# Sheet1.net
KiCad netlist of a schematic drawn in Altium Designer
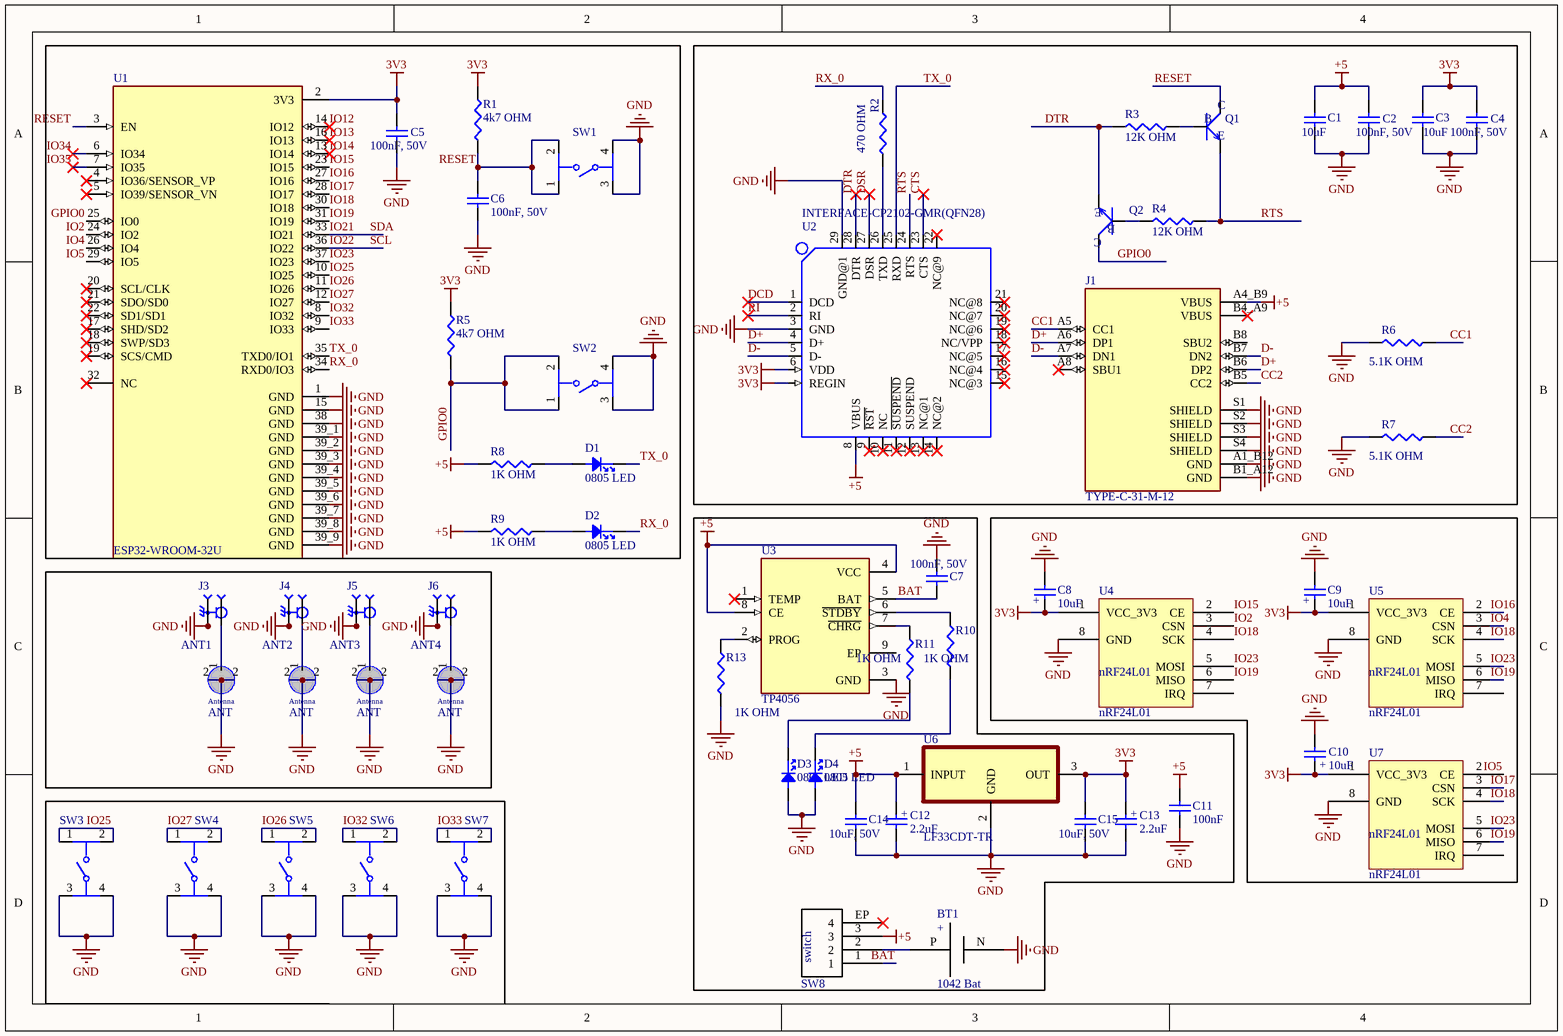
[diagram p0: Sheet1.SchDoc]

(export (version "E")
  (design (tool "Eeschema 10.0.6"))
  (components
    (comp (ref "ANT1")
      (value "ANT")
      (footprint "U.FL SMD")
      (description "U.FL Antenna")
      (libsource (lib "Schlib1") (part "ANT"))
    )
    (comp (ref "ANT2")
      (value "ANT")
      (footprint "U.FL SMD")
      (description "U.FL Antenna")
      (libsource (lib "Schlib1") (part "ANT"))
    )
    (comp (ref "ANT3")
      (value "ANT")
      (footprint "U.FL SMD")
      (description "U.FL Antenna")
      (libsource (lib "Schlib1") (part "ANT"))
    )
    (comp (ref "ANT4")
      (value "ANT")
      (footprint "U.FL SMD")
      (description "U.FL Antenna")
      (libsource (lib "Schlib1") (part "ANT"))
    )
    (comp (ref "BT1") (value "1042 Bat") (footprint "BAT_1042") (libsource (lib "Schlib1") (part "1042")))
    (comp (ref "C1")
      (value "10uF")
      (footprint "CAP0805")
      (description "CAP CER 10UF 0805")
      (fields
        (field (name "MANUFACTURER") "Samsung Electro-Mechanics")
        (field (name "MANUFACTURER PART NUMBER") "CL05B104KB5NNNC")
      )
      (libsource (lib "Schlib1") (part "C0805_10UF"))
    )
    (comp (ref "C2")
      (value "100nF, 50V")
      (footprint "CAP0805")
      (description "CAP CER 0.1UF 0805")
      (fields
        (field (name "MANUFACTURER") "Samsung Electro-Mechanics")
        (field (name "MANUFACTURER PART NUMBER") "CL05B104KB5NNNC")
      )
      (libsource (lib "Schlib1") (part "C0805 100nF"))
    )
    (comp (ref "C3")
      (value "10uF")
      (footprint "CAP0805")
      (description "CAP CER 10UF 0805")
      (fields
        (field (name "MANUFACTURER") "Samsung Electro-Mechanics")
        (field (name "MANUFACTURER PART NUMBER") "CL05B104KB5NNNC")
      )
      (libsource (lib "Schlib1") (part "C0805_10UF"))
    )
    (comp (ref "C4")
      (value "100nF, 50V")
      (footprint "CAP0805")
      (description "CAP CER 0.1UF 0805")
      (fields
        (field (name "MANUFACTURER") "Samsung Electro-Mechanics")
        (field (name "MANUFACTURER PART NUMBER") "CL05B104KB5NNNC")
      )
      (libsource (lib "Schlib1") (part "C0805 100nF"))
    )
    (comp (ref "C5")
      (value "100nF, 50V")
      (footprint "CAP0805")
      (description "CAP CER 0.1UF 0805")
      (fields
        (field (name "MANUFACTURER") "Samsung Electro-Mechanics")
        (field (name "MANUFACTURER PART NUMBER") "CL05B104KB5NNNC")
      )
      (libsource (lib "Schlib1") (part "C0805"))
    )
    (comp (ref "C6")
      (value "100nF, 50V")
      (footprint "CAP0805")
      (description "CAP CER 0.1UF 0805")
      (fields
        (field (name "MANUFACTURER") "Samsung Electro-Mechanics")
        (field (name "MANUFACTURER PART NUMBER") "CL05B104KB5NNNC")
      )
      (libsource (lib "Schlib1") (part "C0805"))
    )
    (comp (ref "C7")
      (value "100nF, 50V")
      (footprint "CAP0805")
      (description "CAP CER 0.1UF 0805")
      (fields
        (field (name "MANUFACTURER") "Samsung Electro-Mechanics")
        (field (name "MANUFACTURER PART NUMBER") "CL05B104KB5NNNC")
      )
      (libsource (lib "Schlib1") (part "C0805 100nF"))
    )
    (comp (ref "C8")
      (value "10uF")
      (footprint "Tan 1206 (3216X18L) Size A")
      (description "Capacitor Tantalum SMD")
      (libsource (lib "Schlib1") (part "10uF Capacitor Tantalum SMD"))
    )
    (comp (ref "C9")
      (value "10uF")
      (footprint "Tan 1206 (3216X18L) Size A")
      (description "Capacitor Tantalum SMD")
      (libsource (lib "Schlib1") (part "10uF Capacitor Tantalum SMD"))
    )
    (comp (ref "C10")
      (value "10uF")
      (footprint "Tan 1206 (3216X18L) Size A")
      (description "Capacitor Tantalum SMD")
      (libsource (lib "Schlib1") (part "Capacitor Tantalum SMD"))
    )
    (comp (ref "C11")
      (value "100nF")
      (footprint "CAP0805")
      (description "CAP CER 100nF 0805")
      (fields
        (field (name "MANUFACTURER") "Samsung Electro-Mechanics")
        (field (name "MANUFACTURER PART NUMBER") "CL05B104KB5NNNC")
      )
      (libsource (lib "Schlib1") (part "C0805_100nF"))
    )
    (comp (ref "C12")
      (value "2.2uF")
      (footprint "Tan 1206 (3216X18L) Size A")
      (description "Capacitor Tantalum SMD")
      (libsource (lib "Schlib1") (part "2.2uF Capacitor Tantalum SMD"))
    )
    (comp (ref "C13")
      (value "2.2uF")
      (footprint "Tan 1206 (3216X18L) Size A")
      (description "Capacitor Tantalum SMD")
      (libsource (lib "Schlib1") (part "2.2uF Capacitor Tantalum SMD"))
    )
    (comp (ref "C14")
      (value "10uF, 50V")
      (footprint "CAP 1206 (3216X15L)")
      (description "CAP CER 10uF 0805, 'CAP 1206 (3216X15L)")
      (fields
        (field (name "MANUFACTURER") "Samsung Electro-Mechanics")
        (field (name "MANUFACTURER PART NUMBER") "CL05B104KB5NNNC")
      )
      (libsource (lib "Schlib1") (part "CAP 10uF (3216X15L)"))
    )
    (comp (ref "C15")
      (value "10uF, 50V")
      (footprint "CAP 1206 (3216X15L)")
      (description "CAP CER 10uF 0805, 'CAP 1206 (3216X15L)")
      (fields
        (field (name "MANUFACTURER") "Samsung Electro-Mechanics")
        (field (name "MANUFACTURER PART NUMBER") "CL05B104KB5NNNC")
      )
      (libsource (lib "Schlib1") (part "CAP 10uF (3216X15L)"))
    )
    (comp (ref "D1")
      (value "0805 LED")
      (footprint "L0805")
      (description "LED RED 0805 SMD")
      (fields
        (field (name "MANUFACTURER") "Vishay")
        (field (name "MANUFACTURER PART NUMBER") "VLMS1500-GS08")
      )
      (libsource (lib "Schlib1") (part "LED 0805"))
    )
    (comp (ref "D2")
      (value "0805 LED")
      (footprint "L0805")
      (description "LED RED 0805 SMD")
      (fields
        (field (name "MANUFACTURER") "Vishay")
        (field (name "MANUFACTURER PART NUMBER") "VLMS1500-GS08")
      )
      (libsource (lib "Schlib1") (part "LED 0805"))
    )
    (comp (ref "D3")
      (value "0805 LED")
      (footprint "L0805")
      (description "LED RED 0805 SMD")
      (fields
        (field (name "MANUFACTURER") "Vishay")
        (field (name "MANUFACTURER PART NUMBER") "VLMS1500-GS08")
      )
      (libsource (lib "Schlib1") (part "LED 0805"))
    )
    (comp (ref "D4")
      (value "0805 LED")
      (footprint "L0805")
      (description "LED RED 0805 SMD")
      (fields
        (field (name "MANUFACTURER") "Vishay")
        (field (name "MANUFACTURER PART NUMBER") "VLMS1500-GS08")
      )
      (libsource (lib "Schlib1") (part "LED 0805"))
    )
    (comp (ref "J1")
      (value "TYPE-C-31-M-12")
      (footprint "HRO_TYPE-C-31-M-12")
      (description "USB Connectors 24 Receptacle 1 8.94*7.3mm RoHS")
      (fields (field (name "MF") "HRO Electronics Co., Ltd."))
      (libsource (lib "Schlib1") (part "TYPE-C-31-M-12"))
    )
    (comp (ref "J3")
      (value "SMA-J-P-H-ST-EM1")
      (footprint "SAMTEC_SMA-J-P-H-ST-EM1")
      (fields (field (name "MF") "Samtec"))
      (libsource (lib "Schlib1") (part "SMA-J-P-H-ST-EM1"))
    )
    (comp (ref "J4")
      (value "SMA-J-P-H-ST-EM1")
      (footprint "SAMTEC_SMA-J-P-H-ST-EM1")
      (fields (field (name "MF") "Samtec"))
      (libsource (lib "Schlib1") (part "SMA-J-P-H-ST-EM1"))
    )
    (comp (ref "J5")
      (value "SMA-J-P-H-ST-EM1")
      (footprint "SAMTEC_SMA-J-P-H-ST-EM1")
      (fields (field (name "MF") "Samtec"))
      (libsource (lib "Schlib1") (part "SMA-J-P-H-ST-EM1"))
    )
    (comp (ref "J6")
      (value "SMA-J-P-H-ST-EM1")
      (footprint "SAMTEC_SMA-J-P-H-ST-EM1")
      (fields (field (name "MF") "Samtec"))
      (libsource (lib "Schlib1") (part "SMA-J-P-H-ST-EM1"))
    )
    (comp (ref "Q1")
      (value "SMD-TRANSISTORS-NPN-25V-500MW(SOT-23)")
      (footprint "SOT-23")
      (description "Bipolar (BJT) Transistor NPN 25 V 500 mA 150MHz 300 mW Surface Mount SOT-23")
      (fields (field (name "MF") "UMW") (field (name "MP") "S8050"))
      (libsource (lib "Schlib1") (part "SMD-TRANSISTORS-NPN-25V-500MW(SOT-23)"))
    )
    (comp (ref "Q2")
      (value "SMD-TRANSISTORS-NPN-25V-500MW(SOT-23)")
      (footprint "SOT-23")
      (description "Bipolar (BJT) Transistor NPN 25 V 500 mA 150MHz 300 mW Surface Mount SOT-23")
      (fields (field (name "MF") "UMW") (field (name "MP") "S8050"))
      (libsource (lib "Schlib1") (part "SMD-TRANSISTORS-NPN-25V-500MW(SOT-23)"))
    )
    (comp (ref "R1")
      (value "4k7 OHM")
      (footprint "RES 0805")
      (description "RES 4.7K OHM 1% 1/16W 0805")
      (fields
        (field (name "MANUFACTURER") "Yageo Group")
        (field (name "MANUFACTURER PART NUMBER") "RC0402FR-074K7L")
      )
      (libsource (lib "Schlib1") (part "RES 0805"))
    )
    (comp (ref "R2")
      (value "470 OHM")
      (footprint "RES 0805")
      (description "RES 470 OHM 1% 1/16W 0805")
      (fields
        (field (name "MANUFACTURER") "Yageo Group")
        (field (name "MANUFACTURER PART NUMBER") "RC0402FR-074K7L")
      )
      (libsource (lib "Schlib1") (part "RES 0805 470 OHM"))
    )
    (comp (ref "R3")
      (value "12K OHM")
      (footprint "RES 0805")
      (description "RES 12K OHM 1% 1/16W 0805")
      (fields
        (field (name "MANUFACTURER") "Yageo Group")
        (field (name "MANUFACTURER PART NUMBER") "RC0402FR-074K7L")
      )
      (libsource (lib "Schlib1") (part "RES 0805 12K OHM"))
    )
    (comp (ref "R4")
      (value "12K OHM")
      (footprint "RES 0805")
      (description "RES 12K OHM 1% 1/16W 0805")
      (fields
        (field (name "MANUFACTURER") "Yageo Group")
        (field (name "MANUFACTURER PART NUMBER") "RC0402FR-074K7L")
      )
      (libsource (lib "Schlib1") (part "RES 0805 12K OHM"))
    )
    (comp (ref "R5")
      (value "4k7 OHM")
      (footprint "RES 0805")
      (description "RES 4.7K OHM 1% 1/16W 0805")
      (fields
        (field (name "MANUFACTURER") "Yageo Group")
        (field (name "MANUFACTURER PART NUMBER") "RC0402FR-074K7L")
      )
      (libsource (lib "Schlib1") (part "RES 0805 4.7K OHM"))
    )
    (comp (ref "R6")
      (value "5.1K OHM")
      (footprint "RES 0805")
      (description "RES 5.1K OHM 1% 1/16W 0805")
      (fields
        (field (name "MANUFACTURER") "Yageo Group")
        (field (name "MANUFACTURER PART NUMBER") "RC0402FR-074K7L")
      )
      (libsource (lib "Schlib1") (part "RES 0805 5.1K OHM"))
    )
    (comp (ref "R7")
      (value "5.1K OHM")
      (footprint "RES 0805")
      (description "RES 5.1K OHM 1% 1/16W 0805")
      (fields
        (field (name "MANUFACTURER") "Yageo Group")
        (field (name "MANUFACTURER PART NUMBER") "RC0402FR-074K7L")
      )
      (libsource (lib "Schlib1") (part "RES 0805 5.1K OHM"))
    )
    (comp (ref "R8")
      (value "1K OHM")
      (footprint "RES 0805")
      (description "RES 4.7K OHM 1% 1/16W 0805")
      (fields
        (field (name "MANUFACTURER") "Yageo Group")
        (field (name "MANUFACTURER PART NUMBER") "RC0402FR-074K7L")
      )
      (libsource (lib "Schlib1") (part "RES 0805 1K OHM"))
    )
    (comp (ref "R9")
      (value "1K OHM")
      (footprint "RES 0805")
      (description "RES 4.7K OHM 1% 1/16W 0805")
      (fields
        (field (name "MANUFACTURER") "Yageo Group")
        (field (name "MANUFACTURER PART NUMBER") "RC0402FR-074K7L")
      )
      (libsource (lib "Schlib1") (part "RES 0805 1K OHM"))
    )
    (comp (ref "R10")
      (value "1K OHM")
      (footprint "RES 0805")
      (description "RES 1K OHM 1% 1/16W 0805")
      (fields
        (field (name "MANUFACTURER") "Yageo Group")
        (field (name "MANUFACTURER PART NUMBER") "RC0402FR-074K7L")
      )
      (libsource (lib "Schlib1") (part "RES 0805 1K OHM"))
    )
    (comp (ref "R11")
      (value "1K OHM")
      (footprint "RES 0805")
      (description "RES 1K OHM 1% 1/16W 0805")
      (fields
        (field (name "MANUFACTURER") "Yageo Group")
        (field (name "MANUFACTURER PART NUMBER") "RC0402FR-074K7L")
      )
      (libsource (lib "Schlib1") (part "RES 0805 1K OHM"))
    )
    (comp (ref "R13")
      (value "1K OHM")
      (footprint "RES 0805")
      (description "RES 1K OHM 1% 1/16W 0805")
      (fields
        (field (name "MANUFACTURER") "Yageo Group")
        (field (name "MANUFACTURER PART NUMBER") "RC0402FR-074K7L")
      )
      (libsource (lib "Schlib1") (part "RES 0805 1K OHM"))
    )
    (comp (ref "SW1")
      (value "PTS645SH50SMTR92LFS")
      (footprint "FP-PTS645SH50SMTR92LFS-MFG")
      (description "SWITCH TACTILE SPST-NO 0.05A 12V")
      (fields (field (name "MANUFACTURER") "C&K Components") (field (name "LCSC PART NUMBER") "C285463"))
      (libsource (lib "Schlib") (part "PTS645SH50SMTR92LFS"))
    )
    (comp (ref "SW2")
      (value "PTS645SH50SMTR92LFS")
      (footprint "FP-PTS645SH50SMTR92LFS-MFG")
      (description "SWITCH TACTILE SPST-NO 0.05A 12V")
      (fields (field (name "MANUFACTURER") "C&K Components") (field (name "LCSC PART NUMBER") "C285463"))
      (libsource (lib "Schlib") (part "PTS645SH50SMTR92LFS"))
    )
    (comp (ref "SW3")
      (value "PTS645SH50SMTR92LFS")
      (footprint "FP-PTS645SH50SMTR92LFS-MFG")
      (description "SWITCH TACTILE SPST-NO 0.05A 12V")
      (fields (field (name "MANUFACTURER") "C&K Components") (field (name "LCSC PART NUMBER") "C285463"))
      (libsource (lib "Schlib1") (part "PTS645SH50SMTR92LFS"))
    )
    (comp (ref "SW4")
      (value "PTS645SH50SMTR92LFS")
      (footprint "FP-PTS645SH50SMTR92LFS-MFG")
      (description "SWITCH TACTILE SPST-NO 0.05A 12V")
      (fields (field (name "MANUFACTURER") "C&K Components") (field (name "LCSC PART NUMBER") "C285463"))
      (libsource (lib "Schlib1") (part "PTS645SH50SMTR92LFS"))
    )
    (comp (ref "SW5")
      (value "PTS645SH50SMTR92LFS")
      (footprint "FP-PTS645SH50SMTR92LFS-MFG")
      (description "SWITCH TACTILE SPST-NO 0.05A 12V")
      (fields (field (name "MANUFACTURER") "C&K Components") (field (name "LCSC PART NUMBER") "C285463"))
      (libsource (lib "Schlib1") (part "PTS645SH50SMTR92LFS"))
    )
    (comp (ref "SW6")
      (value "PTS645SH50SMTR92LFS")
      (footprint "FP-PTS645SH50SMTR92LFS-MFG")
      (description "SWITCH TACTILE SPST-NO 0.05A 12V")
      (fields (field (name "MANUFACTURER") "C&K Components") (field (name "LCSC PART NUMBER") "C285463"))
      (libsource (lib "Schlib1") (part "PTS645SH50SMTR92LFS"))
    )
    (comp (ref "SW7")
      (value "PTS645SH50SMTR92LFS")
      (footprint "FP-PTS645SH50SMTR92LFS-MFG")
      (description "SWITCH TACTILE SPST-NO 0.05A 12V")
      (fields (field (name "MANUFACTURER") "C&K Components") (field (name "LCSC PART NUMBER") "C285463"))
      (libsource (lib "Schlib1") (part "PTS645SH50SMTR92LFS"))
    )
    (comp (ref "SW8")
      (value "SWSLIDT_SPDT_MSS3")
      (footprint "SWSLIDT_SPDT_MSS3")
      (libsource (lib "Schlib1") (part "SlideSwitch"))
    )
    (comp (ref "U1")
      (value "ESP32-WROOM-32U")
      (footprint "XCVR_ESP32-WROOM-32U")
      (fields (field (name "MF") "Espressif Systems"))
      (libsource (lib "Schlib1") (part "ESP32-WROOM-32U"))
    )
    (comp (ref "U2")
      (value "INTERFACE-CP2102-GMR(QFN28)")
      (footprint "QFN28G_0.5-5X5MM")
      (description "USB Bridge, USB to UART USB 2.0 UART Interface 28-QFN (5x5)")
      (fields (field (name "MP") "CP2102-GMR") (field (name "MF") "Silicon Labs"))
      (libsource (lib "Schlib1") (part "INTERFACE-CP2102-GMR(QFN28)"))
    )
    (comp (ref "U3")
      (value "TP4056")
      (footprint "SOP127P600X175-9N")
      (description "Complete single cell Li-Ion battery with a constant current / constant voltage linear charger")
      (fields (field (name "MF") "NanJing Top Power ASIC Corp."))
      (libsource (lib "Schlib1") (part "TP4056"))
    )
    (comp (ref "U4")
      (value "nRF24L01")
      (footprint "NRF24L01_GT24MINI_MS")
      (description "nRF24L01, 2.4GHz Transceiver MODULE, SMD")
      (libsource (lib "Schlib1") (part "nRFL024L01"))
    )
    (comp (ref "U5")
      (value "nRF24L01")
      (footprint "NRF24L01_GT24MINI_MS")
      (description "nRF24L01, 2.4GHz Transceiver MODULE, SMD")
      (libsource (lib "Schlib1") (part "nRFL024L01"))
    )
    (comp (ref "U6")
      (value "LF33CDT-TR")
      (footprint "TO228P972X240-3N")
      (description "Linear Voltage Regulator IC Positive Fixed 1 Output 500mA DPAK")
      (fields (field (name "MF") "STMicroelectronics"))
      (libsource (lib "Schlib1") (part "LF33CDT-TR"))
    )
    (comp (ref "U7")
      (value "nRF24L01")
      (footprint "NRF24L01_GT24MINI_MS")
      (description "nRF24L01, 2.4GHz Transceiver MODULE, SMD")
      (libsource (lib "Schlib1") (part "nRFL024L01"))
    )
  )
  (nets
    (net (code "1") (name "+5") (class "Default")
      (node (ref "C1") (pin "2") (pinfunction "2_2") (pintype "passive"))
      (node (ref "C11") (pin "2") (pinfunction "2_2") (pintype "passive"))
      (node (ref "C12") (pin "1") (pinfunction "1_1") (pintype "passive"))
      (node (ref "C14") (pin "2") (pinfunction "2_2") (pintype "passive"))
      (node (ref "C2") (pin "2") (pinfunction "2_2") (pintype "passive"))
      (node (ref "J1") (pin "A4_B9") (pinfunction "VBUS_A4_B9") (pintype "power_in"))
      (node (ref "R8") (pin "1") (pinfunction "1_1") (pintype "passive"))
      (node (ref "R9") (pin "1") (pinfunction "1_1") (pintype "passive"))
      (node (ref "SW8") (pin "3") (pinfunction "3_3") (pintype "passive"))
      (node (ref "U2") (pin "8") (pinfunction "VBUS_8") (pintype "power_in"))
      (node (ref "U3") (pin "4") (pinfunction "VCC_4") (pintype "power_in"))
      (node (ref "U3") (pin "8") (pinfunction "CE_8") (pintype "input"))
      (node (ref "U6") (pin "1") (pinfunction "INPUT_1") (pintype "power_in"))
    )
    (net (code "2") (name "/BAT") (class "Default")
      (node (ref "C7") (pin "2") (pinfunction "2_2") (pintype "passive"))
      (node (ref "SW8") (pin "1") (pinfunction "1_1") (pintype "passive"))
      (node (ref "U3") (pin "5") (pinfunction "BAT_5") (pintype "output"))
    )
    (net (code "3") (name "/CC1") (class "Default")
      (node (ref "J1") (pin "A5") (pinfunction "CC1_A5") (pintype "bidirectional"))
      (node (ref "R6") (pin "2") (pinfunction "2_2") (pintype "passive"))
    )
    (net (code "4") (name "/CC2") (class "Default")
      (node (ref "J1") (pin "B5") (pinfunction "CC2_B5") (pintype "bidirectional"))
      (node (ref "R7") (pin "2") (pinfunction "2_2") (pintype "passive"))
    )
    (net (code "5") (name "/CTS") (class "Default")
      (node (ref "U2") (pin "23") (pinfunction "CTS_23") (pintype "bidirectional+no_connect"))
    )
    (net (code "6") (name "/D+") (class "Default")
      (node (ref "J1") (pin "A6") (pinfunction "DP1_A6") (pintype "bidirectional"))
      (node (ref "J1") (pin "B6") (pinfunction "DP2_B6") (pintype "bidirectional"))
      (node (ref "U2") (pin "4") (pinfunction "D+_4") (pintype "bidirectional"))
    )
    (net (code "7") (name "/D-") (class "Default")
      (node (ref "J1") (pin "A7") (pinfunction "DN1_A7") (pintype "bidirectional"))
      (node (ref "J1") (pin "B7") (pinfunction "DN2_B7") (pintype "bidirectional"))
      (node (ref "U2") (pin "5") (pinfunction "D-_5") (pintype "bidirectional"))
    )
    (net (code "8") (name "/DCD") (class "Default")
      (node (ref "U2") (pin "1") (pinfunction "DCD_1") (pintype "bidirectional+no_connect"))
    )
    (net (code "9") (name "/DSR") (class "Default")
      (node (ref "U2") (pin "27") (pinfunction "DSR_27") (pintype "bidirectional+no_connect"))
    )
    (net (code "10") (name "/DTR") (class "Default")
      (node (ref "Q2") (pin "2") (pinfunction "E_2") (pintype "passive"))
      (node (ref "R3") (pin "1") (pinfunction "1_1") (pintype "passive"))
      (node (ref "U2") (pin "28") (pinfunction "DTR_28") (pintype "bidirectional"))
    )
    (net (code "11") (name "/GPIO0") (class "Default")
      (node (ref "Q2") (pin "3") (pinfunction "C_3") (pintype "passive"))
      (node (ref "R5") (pin "1") (pinfunction "1_1") (pintype "passive"))
      (node (ref "SW2") (pin "1") (pinfunction "1_1") (pintype "passive"))
      (node (ref "SW2") (pin "2") (pinfunction "2_2") (pintype "passive"))
      (node (ref "U1") (pin "25") (pinfunction "IO0_25") (pintype "bidirectional"))
    )
    (net (code "12") (name "/IO2") (class "Default")
      (node (ref "U1") (pin "24") (pinfunction "IO2_24") (pintype "bidirectional"))
      (node (ref "U4") (pin "3") (pinfunction "CSN_3") (pintype "passive"))
    )
    (net (code "13") (name "/IO4") (class "Default")
      (node (ref "U1") (pin "26") (pinfunction "IO4_26") (pintype "bidirectional"))
      (node (ref "U5") (pin "3") (pinfunction "CSN_3") (pintype "passive"))
    )
    (net (code "14") (name "/IO5") (class "Default")
      (node (ref "U1") (pin "29") (pinfunction "IO5_29") (pintype "bidirectional"))
      (node (ref "U7") (pin "2") (pinfunction "CE_2") (pintype "passive"))
    )
    (net (code "15") (name "/IO12") (class "Default")
      (node (ref "U1") (pin "14") (pinfunction "IO12_14") (pintype "bidirectional+no_connect"))
    )
    (net (code "16") (name "/IO13") (class "Default")
      (node (ref "U1") (pin "16") (pinfunction "IO13_16") (pintype "bidirectional+no_connect"))
    )
    (net (code "17") (name "/IO14") (class "Default")
      (node (ref "U1") (pin "13") (pinfunction "IO14_13") (pintype "bidirectional+no_connect"))
    )
    (net (code "18") (name "/IO15") (class "Default")
      (node (ref "U1") (pin "23") (pinfunction "IO15_23") (pintype "bidirectional"))
      (node (ref "U4") (pin "2") (pinfunction "CE_2") (pintype "passive"))
    )
    (net (code "19") (name "/IO16") (class "Default")
      (node (ref "U1") (pin "27") (pinfunction "IO16_27") (pintype "bidirectional"))
      (node (ref "U5") (pin "2") (pinfunction "CE_2") (pintype "passive"))
    )
    (net (code "20") (name "/IO17") (class "Default")
      (node (ref "U1") (pin "28") (pinfunction "IO17_28") (pintype "bidirectional"))
      (node (ref "U7") (pin "3") (pinfunction "CSN_3") (pintype "passive"))
    )
    (net (code "21") (name "/IO18") (class "Default")
      (node (ref "U1") (pin "30") (pinfunction "IO18_30") (pintype "bidirectional"))
      (node (ref "U4") (pin "4") (pinfunction "SCK_4") (pintype "passive"))
      (node (ref "U5") (pin "4") (pinfunction "SCK_4") (pintype "passive"))
      (node (ref "U7") (pin "4") (pinfunction "SCK_4") (pintype "passive"))
    )
    (net (code "22") (name "/IO19") (class "Default")
      (node (ref "U1") (pin "31") (pinfunction "IO19_31") (pintype "bidirectional"))
      (node (ref "U4") (pin "6") (pinfunction "MISO_6") (pintype "passive"))
      (node (ref "U5") (pin "6") (pinfunction "MISO_6") (pintype "passive"))
      (node (ref "U7") (pin "6") (pinfunction "MISO_6") (pintype "passive"))
    )
    (net (code "23") (name "/IO21") (class "Default")
      (node (ref "U1") (pin "33") (pinfunction "IO21_33") (pintype "bidirectional"))
    )
    (net (code "24") (name "/IO22") (class "Default")
      (node (ref "U1") (pin "36") (pinfunction "IO22_36") (pintype "bidirectional"))
    )
    (net (code "25") (name "/IO23") (class "Default")
      (node (ref "U1") (pin "37") (pinfunction "IO23_37") (pintype "bidirectional"))
      (node (ref "U4") (pin "5") (pinfunction "MOSI_5") (pintype "passive"))
      (node (ref "U5") (pin "5") (pinfunction "MOSI_5") (pintype "passive"))
      (node (ref "U7") (pin "5") (pinfunction "MOSI_5") (pintype "passive"))
    )
    (net (code "26") (name "/IO25") (class "Default")
      (node (ref "SW3") (pin "1") (pinfunction "1_1") (pintype "passive"))
      (node (ref "SW3") (pin "2") (pinfunction "2_2") (pintype "passive"))
      (node (ref "U1") (pin "10") (pinfunction "IO25_10") (pintype "bidirectional"))
    )
    (net (code "27") (name "/IO26") (class "Default")
      (node (ref "SW5") (pin "1") (pinfunction "1_1") (pintype "passive"))
      (node (ref "SW5") (pin "2") (pinfunction "2_2") (pintype "passive"))
      (node (ref "U1") (pin "11") (pinfunction "IO26_11") (pintype "bidirectional"))
    )
    (net (code "28") (name "/IO27") (class "Default")
      (node (ref "SW4") (pin "1") (pinfunction "1_1") (pintype "passive"))
      (node (ref "SW4") (pin "2") (pinfunction "2_2") (pintype "passive"))
      (node (ref "U1") (pin "12") (pinfunction "IO27_12") (pintype "bidirectional"))
    )
    (net (code "29") (name "/IO32") (class "Default")
      (node (ref "SW6") (pin "1") (pinfunction "1_1") (pintype "passive"))
      (node (ref "SW6") (pin "2") (pinfunction "2_2") (pintype "passive"))
      (node (ref "U1") (pin "8") (pinfunction "IO32_8") (pintype "bidirectional"))
    )
    (net (code "30") (name "/IO33") (class "Default")
      (node (ref "SW7") (pin "1") (pinfunction "1_1") (pintype "passive"))
      (node (ref "SW7") (pin "2") (pinfunction "2_2") (pintype "passive"))
      (node (ref "U1") (pin "9") (pinfunction "IO33_9") (pintype "bidirectional"))
    )
    (net (code "31") (name "/IO34") (class "Default")
      (node (ref "U1") (pin "6") (pinfunction "IO34_6") (pintype "input+no_connect"))
    )
    (net (code "32") (name "/IO35") (class "Default")
      (node (ref "U1") (pin "7") (pinfunction "IO35_7") (pintype "input+no_connect"))
    )
    (net (code "33") (name "/RESET") (class "Default")
      (node (ref "C6") (pin "2") (pinfunction "2_2") (pintype "passive"))
      (node (ref "Q1") (pin "3") (pinfunction "C_3") (pintype "passive"))
      (node (ref "R1") (pin "1") (pinfunction "1_1") (pintype "passive"))
      (node (ref "SW1") (pin "1") (pinfunction "1_1") (pintype "passive"))
      (node (ref "SW1") (pin "2") (pinfunction "2_2") (pintype "passive"))
      (node (ref "U1") (pin "3") (pinfunction "EN_3") (pintype "input"))
    )
    (net (code "34") (name "/RI") (class "Default")
      (node (ref "U2") (pin "2") (pinfunction "RI_2") (pintype "bidirectional+no_connect"))
    )
    (net (code "35") (name "/RTS") (class "Default")
      (node (ref "Q1") (pin "2") (pinfunction "E_2") (pintype "passive"))
      (node (ref "R4") (pin "2") (pinfunction "2_2") (pintype "passive"))
      (node (ref "U2") (pin "24") (pinfunction "RTS_24") (pintype "bidirectional"))
    )
    (net (code "36") (name "/RX_0") (class "Default")
      (node (ref "D2") (pin "k") (pinfunction "1_k") (pintype "passive"))
      (node (ref "R2") (pin "2") (pinfunction "2_2") (pintype "passive"))
      (node (ref "U1") (pin "34") (pinfunction "RXD0/IO3_34") (pintype "bidirectional"))
    )
    (net (code "37") (name "/TX_0") (class "Default")
      (node (ref "D1") (pin "k") (pinfunction "1_k") (pintype "passive"))
      (node (ref "U1") (pin "35") (pinfunction "TXD0/IO1_35") (pintype "bidirectional"))
      (node (ref "U2") (pin "25") (pinfunction "RXD_25") (pintype "bidirectional"))
    )
    (net (code "38") (name "3V3") (class "Default")
      (node (ref "C10") (pin "2") (pinfunction "2_2") (pintype "passive"))
      (node (ref "C13") (pin "1") (pinfunction "1_1") (pintype "passive"))
      (node (ref "C15") (pin "2") (pinfunction "2_2") (pintype "passive"))
      (node (ref "C3") (pin "2") (pinfunction "2_2") (pintype "passive"))
      (node (ref "C4") (pin "2") (pinfunction "2_2") (pintype "passive"))
      (node (ref "C5") (pin "2") (pinfunction "2_2") (pintype "passive"))
      (node (ref "C8") (pin "1") (pinfunction "1_1") (pintype "passive"))
      (node (ref "C9") (pin "1") (pinfunction "1_1") (pintype "passive"))
      (node (ref "R1") (pin "2") (pinfunction "2_2") (pintype "passive"))
      (node (ref "R5") (pin "2") (pinfunction "2_2") (pintype "passive"))
      (node (ref "U1") (pin "2") (pinfunction "3V3_2") (pintype "power_in"))
      (node (ref "U2") (pin "6") (pinfunction "VDD_6") (pintype "input"))
      (node (ref "U2") (pin "7") (pinfunction "REGIN_7") (pintype "input"))
      (node (ref "U4") (pin "1") (pinfunction "VCC_3V3_1") (pintype "passive"))
      (node (ref "U5") (pin "1") (pinfunction "VCC_3V3_1") (pintype "passive"))
      (node (ref "U6") (pin "3") (pinfunction "OUT_3") (pintype "power_in"))
      (node (ref "U7") (pin "1") (pinfunction "VCC_3V3_1") (pintype "passive"))
    )
    (net (code "39") (name "GND") (class "Default")
      (node (ref "ANT1") (pin "2") (pinfunction "2_2") (pintype "passive"))
      (node (ref "ANT2") (pin "2") (pinfunction "2_2") (pintype "passive"))
      (node (ref "ANT3") (pin "2") (pinfunction "2_2") (pintype "passive"))
      (node (ref "ANT4") (pin "2") (pinfunction "2_2") (pintype "passive"))
      (node (ref "BT1") (pin "N") (pinfunction "N_N") (pintype "passive"))
      (node (ref "C1") (pin "1") (pinfunction "1_1") (pintype "passive"))
      (node (ref "C10") (pin "1") (pinfunction "1_1") (pintype "passive"))
      (node (ref "C11") (pin "1") (pinfunction "1_1") (pintype "passive"))
      (node (ref "C12") (pin "2") (pinfunction "2_2") (pintype "passive"))
      (node (ref "C13") (pin "2") (pinfunction "2_2") (pintype "passive"))
      (node (ref "C14") (pin "1") (pinfunction "1_1") (pintype "passive"))
      (node (ref "C15") (pin "1") (pinfunction "1_1") (pintype "passive"))
      (node (ref "C2") (pin "1") (pinfunction "1_1") (pintype "passive"))
      (node (ref "C3") (pin "1") (pinfunction "1_1") (pintype "passive"))
      (node (ref "C4") (pin "1") (pinfunction "1_1") (pintype "passive"))
      (node (ref "C5") (pin "1") (pinfunction "1_1") (pintype "passive"))
      (node (ref "C6") (pin "1") (pinfunction "1_1") (pintype "passive"))
      (node (ref "C7") (pin "1") (pinfunction "1_1") (pintype "passive"))
      (node (ref "C8") (pin "2") (pinfunction "2_2") (pintype "passive"))
      (node (ref "C9") (pin "2") (pinfunction "2_2") (pintype "passive"))
      (node (ref "D3") (pin "A") (pinfunction "2_A") (pintype "passive"))
      (node (ref "D4") (pin "A") (pinfunction "2_A") (pintype "passive"))
      (node (ref "J1") (pin "A1_B12") (pinfunction "GND_A1_B12") (pintype "power_in"))
      (node (ref "J1") (pin "B1_A12") (pinfunction "GND_B1_A12") (pintype "power_in"))
      (node (ref "J1") (pin "S1") (pinfunction "SHIELD_S1") (pintype "passive"))
      (node (ref "J1") (pin "S2") (pinfunction "SHIELD_S2") (pintype "passive"))
      (node (ref "J1") (pin "S3") (pinfunction "SHIELD_S3") (pintype "passive"))
      (node (ref "J1") (pin "S4") (pinfunction "SHIELD_S4") (pintype "passive"))
      (node (ref "J3") (pin "2_1") (pinfunction "2_2_1") (pintype "passive"))
      (node (ref "J3") (pin "2_2") (pinfunction "2_2_2") (pintype "passive"))
      (node (ref "J3") (pin "3_1") (pinfunction "2_3_1") (pintype "passive"))
      (node (ref "J3") (pin "3_2") (pinfunction "2_3_2") (pintype "passive"))
      (node (ref "J4") (pin "2_1") (pinfunction "2_2_1") (pintype "passive"))
      (node (ref "J4") (pin "2_2") (pinfunction "2_2_2") (pintype "passive"))
      (node (ref "J4") (pin "3_1") (pinfunction "2_3_1") (pintype "passive"))
      (node (ref "J4") (pin "3_2") (pinfunction "2_3_2") (pintype "passive"))
      (node (ref "J5") (pin "2_1") (pinfunction "2_2_1") (pintype "passive"))
      (node (ref "J5") (pin "2_2") (pinfunction "2_2_2") (pintype "passive"))
      (node (ref "J5") (pin "3_1") (pinfunction "2_3_1") (pintype "passive"))
      (node (ref "J5") (pin "3_2") (pinfunction "2_3_2") (pintype "passive"))
      (node (ref "J6") (pin "2_1") (pinfunction "2_2_1") (pintype "passive"))
      (node (ref "J6") (pin "2_2") (pinfunction "2_2_2") (pintype "passive"))
      (node (ref "J6") (pin "3_1") (pinfunction "2_3_1") (pintype "passive"))
      (node (ref "J6") (pin "3_2") (pinfunction "2_3_2") (pintype "passive"))
      (node (ref "R13") (pin "1") (pinfunction "1_1") (pintype "passive"))
      (node (ref "R6") (pin "1") (pinfunction "1_1") (pintype "passive"))
      (node (ref "R7") (pin "1") (pinfunction "1_1") (pintype "passive"))
      (node (ref "SW1") (pin "3") (pinfunction "3_3") (pintype "passive"))
      (node (ref "SW1") (pin "4") (pinfunction "4_4") (pintype "passive"))
      (node (ref "SW2") (pin "3") (pinfunction "3_3") (pintype "passive"))
      (node (ref "SW2") (pin "4") (pinfunction "4_4") (pintype "passive"))
      (node (ref "SW3") (pin "3") (pinfunction "3_3") (pintype "passive"))
      (node (ref "SW3") (pin "4") (pinfunction "4_4") (pintype "passive"))
      (node (ref "SW4") (pin "3") (pinfunction "3_3") (pintype "passive"))
      (node (ref "SW4") (pin "4") (pinfunction "4_4") (pintype "passive"))
      (node (ref "SW5") (pin "3") (pinfunction "3_3") (pintype "passive"))
      (node (ref "SW5") (pin "4") (pinfunction "4_4") (pintype "passive"))
      (node (ref "SW6") (pin "3") (pinfunction "3_3") (pintype "passive"))
      (node (ref "SW6") (pin "4") (pinfunction "4_4") (pintype "passive"))
      (node (ref "SW7") (pin "3") (pinfunction "3_3") (pintype "passive"))
      (node (ref "SW7") (pin "4") (pinfunction "4_4") (pintype "passive"))
      (node (ref "U1") (pin "1") (pinfunction "GND_1") (pintype "power_in"))
      (node (ref "U1") (pin "15") (pinfunction "GND_15") (pintype "power_in"))
      (node (ref "U1") (pin "38") (pinfunction "GND_38") (pintype "power_in"))
      (node (ref "U1") (pin "39_1") (pinfunction "GND_39_1") (pintype "power_in"))
      (node (ref "U1") (pin "39_2") (pinfunction "GND_39_2") (pintype "power_in"))
      (node (ref "U1") (pin "39_3") (pinfunction "GND_39_3") (pintype "power_in"))
      (node (ref "U1") (pin "39_4") (pinfunction "GND_39_4") (pintype "power_in"))
      (node (ref "U1") (pin "39_5") (pinfunction "GND_39_5") (pintype "power_in"))
      (node (ref "U1") (pin "39_6") (pinfunction "GND_39_6") (pintype "power_in"))
      (node (ref "U1") (pin "39_7") (pinfunction "GND_39_7") (pintype "power_in"))
      (node (ref "U1") (pin "39_8") (pinfunction "GND_39_8") (pintype "power_in"))
      (node (ref "U1") (pin "39_9") (pinfunction "GND_39_9") (pintype "power_in"))
      (node (ref "U2") (pin "29") (pinfunction "GND@1_29") (pintype "power_in"))
      (node (ref "U2") (pin "3") (pinfunction "GND_3") (pintype "power_in"))
      (node (ref "U3") (pin "3") (pinfunction "GND_3") (pintype "power_in"))
      (node (ref "U4") (pin "8") (pinfunction "GND_8") (pintype "passive"))
      (node (ref "U5") (pin "8") (pinfunction "GND_8") (pintype "passive"))
      (node (ref "U6") (pin "2") (pinfunction "GND_2") (pintype "passive"))
      (node (ref "U7") (pin "8") (pinfunction "GND_8") (pintype "passive"))
    )
    (net (code "40") (name "Net-(ANT1-Pad1)") (class "Default")
      (node (ref "ANT1") (pin "1") (pinfunction "1_1") (pintype "passive"))
      (node (ref "J3") (pin "1") (pinfunction "1_1") (pintype "passive"))
    )
    (net (code "41") (name "Net-(ANT2-Pad1)") (class "Default")
      (node (ref "ANT2") (pin "1") (pinfunction "1_1") (pintype "passive"))
      (node (ref "J4") (pin "1") (pinfunction "1_1") (pintype "passive"))
    )
    (net (code "42") (name "Net-(ANT3-Pad1)") (class "Default")
      (node (ref "ANT3") (pin "1") (pinfunction "1_1") (pintype "passive"))
      (node (ref "J5") (pin "1") (pinfunction "1_1") (pintype "passive"))
    )
    (net (code "43") (name "Net-(ANT4-Pad1)") (class "Default")
      (node (ref "ANT4") (pin "1") (pinfunction "1_1") (pintype "passive"))
      (node (ref "J6") (pin "1") (pinfunction "1_1") (pintype "passive"))
    )
    (net (code "44") (name "Net-(BT1-PadP)") (class "Default")
      (node (ref "BT1") (pin "P") (pinfunction "P_P") (pintype "passive"))
      (node (ref "SW8") (pin "2") (pinfunction "2_2") (pintype "passive"))
    )
    (net (code "45") (name "Net-(D1-2)") (class "Default")
      (node (ref "D1") (pin "A") (pinfunction "2_A") (pintype "passive"))
      (node (ref "R8") (pin "2") (pinfunction "2_2") (pintype "passive"))
    )
    (net (code "46") (name "Net-(D2-2)") (class "Default")
      (node (ref "D2") (pin "A") (pinfunction "2_A") (pintype "passive"))
      (node (ref "R9") (pin "2") (pinfunction "2_2") (pintype "passive"))
    )
    (net (code "47") (name "Net-(D3-1)") (class "Default")
      (node (ref "D3") (pin "k") (pinfunction "1_k") (pintype "passive"))
      (node (ref "R11") (pin "1") (pinfunction "1_1") (pintype "passive"))
    )
    (net (code "48") (name "Net-(D4-1)") (class "Default")
      (node (ref "D4") (pin "k") (pinfunction "1_k") (pintype "passive"))
      (node (ref "R10") (pin "2") (pinfunction "2_2") (pintype "passive"))
    )
    (net (code "49") (name "Net-(Q1-B)") (class "Default")
      (node (ref "Q1") (pin "1") (pinfunction "B_1") (pintype "passive"))
      (node (ref "R3") (pin "2") (pinfunction "2_2") (pintype "passive"))
    )
    (net (code "50") (name "Net-(Q2-B)") (class "Default")
      (node (ref "Q2") (pin "1") (pinfunction "B_1") (pintype "passive"))
      (node (ref "R4") (pin "1") (pinfunction "1_1") (pintype "passive"))
    )
    (net (code "51") (name "Net-(U2-TXD)") (class "Default")
      (node (ref "R2") (pin "1") (pinfunction "1_1") (pintype "passive"))
      (node (ref "U2") (pin "26") (pinfunction "TXD_26") (pintype "bidirectional"))
    )
    (net (code "52") (name "Net-(U3-PROG)") (class "Default")
      (node (ref "R13") (pin "2") (pinfunction "2_2") (pintype "passive"))
      (node (ref "U3") (pin "2") (pinfunction "PROG_2") (pintype "bidirectional"))
    )
    (net (code "53") (name "Net-(U3-~{CHRG})") (class "Default")
      (node (ref "R11") (pin "2") (pinfunction "2_2") (pintype "passive"))
      (node (ref "U3") (pin "7") (pinfunction "~{CHRG}_7") (pintype "output"))
    )
    (net (code "54") (name "Net-(U3-~{STDBY})") (class "Default")
      (node (ref "R10") (pin "1") (pinfunction "1_1") (pintype "passive"))
      (node (ref "U3") (pin "6") (pinfunction "~{STDBY}_6") (pintype "output"))
    )
    (net (code "55") (name "unconnected-(J1-SBU1-PadA8)") (class "Default")
      (node (ref "J1") (pin "A8") (pinfunction "SBU1_A8") (pintype "bidirectional+no_connect"))
    )
    (net (code "56") (name "unconnected-(J1-SBU2-PadB8)") (class "Default")
      (node (ref "J1") (pin "B8") (pinfunction "SBU2_B8") (pintype "bidirectional"))
    )
    (net (code "57") (name "unconnected-(J1-VBUS-PadB4_A9)") (class "Default")
      (node (ref "J1") (pin "B4_A9") (pinfunction "VBUS_B4_A9") (pintype "power_in+no_connect"))
    )
    (net (code "58") (name "unconnected-(SW8-4-PadEP)") (class "Default")
      (node (ref "SW8") (pin "EP") (pinfunction "4_EP") (pintype "passive+no_connect"))
    )
    (net (code "59") (name "unconnected-(U1-IO36{slash}SENSOR_VP-Pad4)") (class "Default")
      (node (ref "U1") (pin "4") (pinfunction "IO36/SENSOR_VP_4") (pintype "input+no_connect"))
    )
    (net (code "60") (name "unconnected-(U1-IO39{slash}SENSOR_VN-Pad5)") (class "Default")
      (node (ref "U1") (pin "5") (pinfunction "IO39/SENSOR_VN_5") (pintype "input+no_connect"))
    )
    (net (code "61") (name "unconnected-(U1-NC-Pad32)") (class "Default")
      (node (ref "U1") (pin "32") (pinfunction "NC_32") (pintype "passive+no_connect"))
    )
    (net (code "62") (name "unconnected-(U1-SCL{slash}CLK-Pad20)") (class "Default")
      (node (ref "U1") (pin "20") (pinfunction "SCL/CLK_20") (pintype "bidirectional+no_connect"))
    )
    (net (code "63") (name "unconnected-(U1-SCS{slash}CMD-Pad19)") (class "Default")
      (node (ref "U1") (pin "19") (pinfunction "SCS/CMD_19") (pintype "bidirectional+no_connect"))
    )
    (net (code "64") (name "unconnected-(U1-SD1{slash}SD1-Pad22)") (class "Default")
      (node (ref "U1") (pin "22") (pinfunction "SD1/SD1_22") (pintype "bidirectional+no_connect"))
    )
    (net (code "65") (name "unconnected-(U1-SDO{slash}SD0-Pad21)") (class "Default")
      (node (ref "U1") (pin "21") (pinfunction "SDO/SD0_21") (pintype "bidirectional+no_connect"))
    )
    (net (code "66") (name "unconnected-(U1-SHD{slash}SD2-Pad17)") (class "Default")
      (node (ref "U1") (pin "17") (pinfunction "SHD/SD2_17") (pintype "bidirectional+no_connect"))
    )
    (net (code "67") (name "unconnected-(U1-SWP{slash}SD3-Pad18)") (class "Default")
      (node (ref "U1") (pin "18") (pinfunction "SWP/SD3_18") (pintype "bidirectional+no_connect"))
    )
    (net (code "68") (name "unconnected-(U2-NC-Pad10)") (class "Default")
      (node (ref "U2") (pin "10") (pinfunction "NC_10") (pintype "bidirectional+no_connect"))
    )
    (net (code "69") (name "unconnected-(U2-NC@1-Pad13)") (class "Default")
      (node (ref "U2") (pin "13") (pinfunction "NC@1_13") (pintype "bidirectional+no_connect"))
    )
    (net (code "70") (name "unconnected-(U2-NC@2-Pad14)") (class "Default")
      (node (ref "U2") (pin "14") (pinfunction "NC@2_14") (pintype "bidirectional+no_connect"))
    )
    (net (code "71") (name "unconnected-(U2-NC@3-Pad15)") (class "Default")
      (node (ref "U2") (pin "15") (pinfunction "NC@3_15") (pintype "bidirectional+no_connect"))
    )
    (net (code "72") (name "unconnected-(U2-NC@4-Pad16)") (class "Default")
      (node (ref "U2") (pin "16") (pinfunction "NC@4_16") (pintype "bidirectional+no_connect"))
    )
    (net (code "73") (name "unconnected-(U2-NC@5-Pad17)") (class "Default")
      (node (ref "U2") (pin "17") (pinfunction "NC@5_17") (pintype "bidirectional+no_connect"))
    )
    (net (code "74") (name "unconnected-(U2-NC@6-Pad19)") (class "Default")
      (node (ref "U2") (pin "19") (pinfunction "NC@6_19") (pintype "bidirectional+no_connect"))
    )
    (net (code "75") (name "unconnected-(U2-NC@7-Pad20)") (class "Default")
      (node (ref "U2") (pin "20") (pinfunction "NC@7_20") (pintype "bidirectional+no_connect"))
    )
    (net (code "76") (name "unconnected-(U2-NC@8-Pad21)") (class "Default")
      (node (ref "U2") (pin "21") (pinfunction "NC@8_21") (pintype "bidirectional+no_connect"))
    )
    (net (code "77") (name "unconnected-(U2-NC@9-Pad22)") (class "Default")
      (node (ref "U2") (pin "22") (pinfunction "NC@9_22") (pintype "bidirectional+no_connect"))
    )
    (net (code "78") (name "unconnected-(U2-NC{slash}VPP-Pad18)") (class "Default")
      (node (ref "U2") (pin "18") (pinfunction "NC/VPP_18") (pintype "bidirectional+no_connect"))
    )
    (net (code "79") (name "unconnected-(U2-SUSPEND-Pad12)") (class "Default")
      (node (ref "U2") (pin "12") (pinfunction "SUSPEND_12") (pintype "bidirectional+no_connect"))
    )
    (net (code "80") (name "unconnected-(U2-~{RST}-Pad9)") (class "Default")
      (node (ref "U2") (pin "9") (pinfunction "~{RST}_9") (pintype "bidirectional+no_connect"))
    )
    (net (code "81") (name "unconnected-(U2-~{SUSPEND}-Pad11)") (class "Default")
      (node (ref "U2") (pin "11") (pinfunction "~{SUSPEND}_11") (pintype "bidirectional+no_connect"))
    )
    (net (code "82") (name "unconnected-(U3-EP-Pad9)") (class "Default")
      (node (ref "U3") (pin "9") (pinfunction "EP_9") (pintype "passive"))
    )
    (net (code "83") (name "unconnected-(U3-TEMP-Pad1)") (class "Default")
      (node (ref "U3") (pin "1") (pinfunction "TEMP_1") (pintype "input+no_connect"))
    )
    (net (code "84") (name "unconnected-(U4-IRQ-Pad7)") (class "Default")
      (node (ref "U4") (pin "7") (pinfunction "IRQ_7") (pintype "passive"))
    )
    (net (code "85") (name "unconnected-(U5-IRQ-Pad7)") (class "Default")
      (node (ref "U5") (pin "7") (pinfunction "IRQ_7") (pintype "passive"))
    )
    (net (code "86") (name "unconnected-(U7-IRQ-Pad7)") (class "Default")
      (node (ref "U7") (pin "7") (pinfunction "IRQ_7") (pintype "passive"))
    )
  )
)
